# Power_Board.net
KiCad netlist of a schematic drawn in Altium Designer
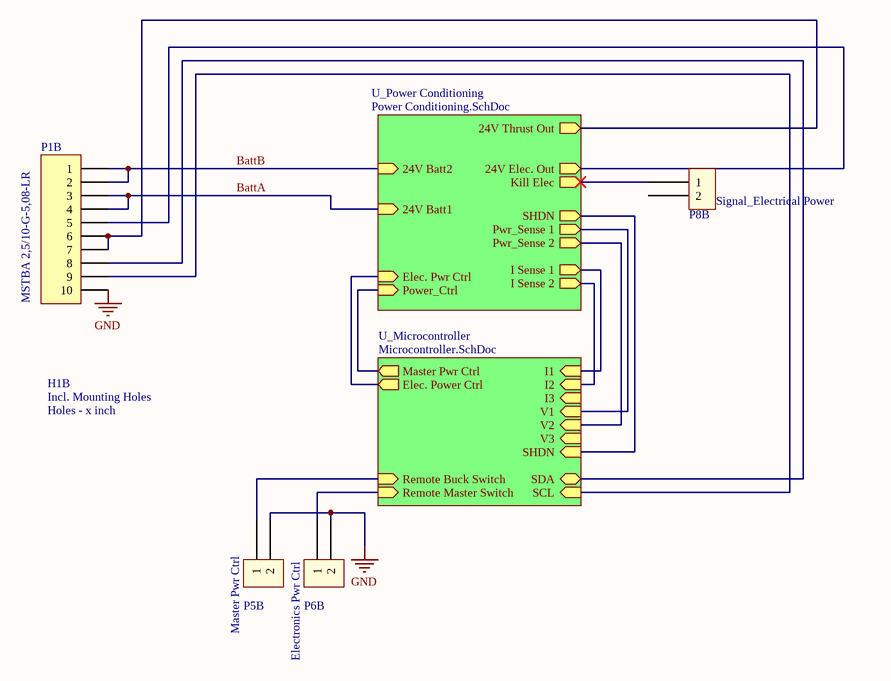
[diagram p0: Power Board.SchDoc]

(export (version "E")
  (design (tool "Eeschema 10.0.6"))
  (components
    (comp (ref "H1B")
      (value "Holes - x inch")
      (footprint "110mil Holes - 2.5  Inch")
      (libsource (lib "URC") (part "Holes - x inch"))
    )
    (comp (ref "P1B")
      (value "MSTBA 2,5/10-G-5,08")
      (footprint "MSTBA 2,5/10-G-5,08")
      (description "Header, 10-Pin")
      (fields (field (name "MANUFACTURER PART NUMBER") "MSTBA 2,5/10-G-5,08-LR"))
      (libsource (lib "Pheonix Connectors") (part "MSTBA 2,5/10-G-5,08"))
    )
    (comp (ref "P5B")
      (value "Header")
      (footprint "1x2 Header")
      (description "1x2 Header")
      (libsource (lib "URC_Lib") (part "1x2 Header"))
    )
    (comp (ref "P6B")
      (value "Header")
      (footprint "1x2 Header")
      (description "1x2 Header")
      (libsource (lib "URC_Lib") (part "1x2 Header"))
    )
    (comp (ref "P8B")
      (value "Header")
      (footprint "1x2 Header")
      (description "1x2 Header")
      (libsource (lib "") (part "1x2 Header_1"))
    )
  )
  (nets
    (net (code "1") (name "/24V Elec. Out") (class "Default")
      (node (ref "P1B") (pin "5") (pinfunction "5_5") (pintype "passive"))
    )
    (net (code "2") (name "/24V Thrust Out") (class "Default")
      (node (ref "P1B") (pin "6") (pinfunction "6_6") (pintype "passive"))
      (node (ref "P1B") (pin "7") (pinfunction "7_7") (pintype "passive"))
    )
    (net (code "3") (name "/BattA") (class "Default")
      (node (ref "P1B") (pin "3") (pinfunction "3_3") (pintype "passive"))
      (node (ref "P1B") (pin "4") (pinfunction "4_4") (pintype "passive"))
    )
    (net (code "4") (name "/BattB") (class "Default")
      (node (ref "P1B") (pin "1") (pinfunction "1_1") (pintype "passive"))
      (node (ref "P1B") (pin "2") (pinfunction "2_2") (pintype "passive"))
    )
    (net (code "9") (name "/Kill Elec") (class "Default")
      (node (ref "P8B") (pin "1") (pinfunction "1_1") (pintype "passive+no_connect"))
    )
    (net (code "13") (name "/Remote Buck Switch") (class "Default")
      (node (ref "P5B") (pin "1") (pinfunction "1_1") (pintype "passive"))
    )
    (net (code "14") (name "/Remote Master Switch") (class "Default")
      (node (ref "P6B") (pin "1") (pinfunction "1_1") (pintype "passive"))
    )
    (net (code "15") (name "/SCL") (class "Default")
      (node (ref "P1B") (pin "9") (pinfunction "9_9") (pintype "passive"))
    )
    (net (code "16") (name "/SDA") (class "Default")
      (node (ref "P1B") (pin "8") (pinfunction "8_8") (pintype "passive"))
    )
    (net (code "19") (name "GND") (class "Default")
      (node (ref "P1B") (pin "10") (pinfunction "10_10") (pintype "passive"))
      (node (ref "P5B") (pin "2") (pinfunction "2_2") (pintype "passive"))
      (node (ref "P6B") (pin "2") (pinfunction "2_2") (pintype "passive"))
    )
    (net (code "20") (name "unconnected-(P8B-Pad2)") (class "Default")
      (node (ref "P8B") (pin "2") (pinfunction "2_2") (pintype "passive"))
    )
  )
)
